# nglight-mini.net
KiCad netlist of a schematic drawn in EAGLE
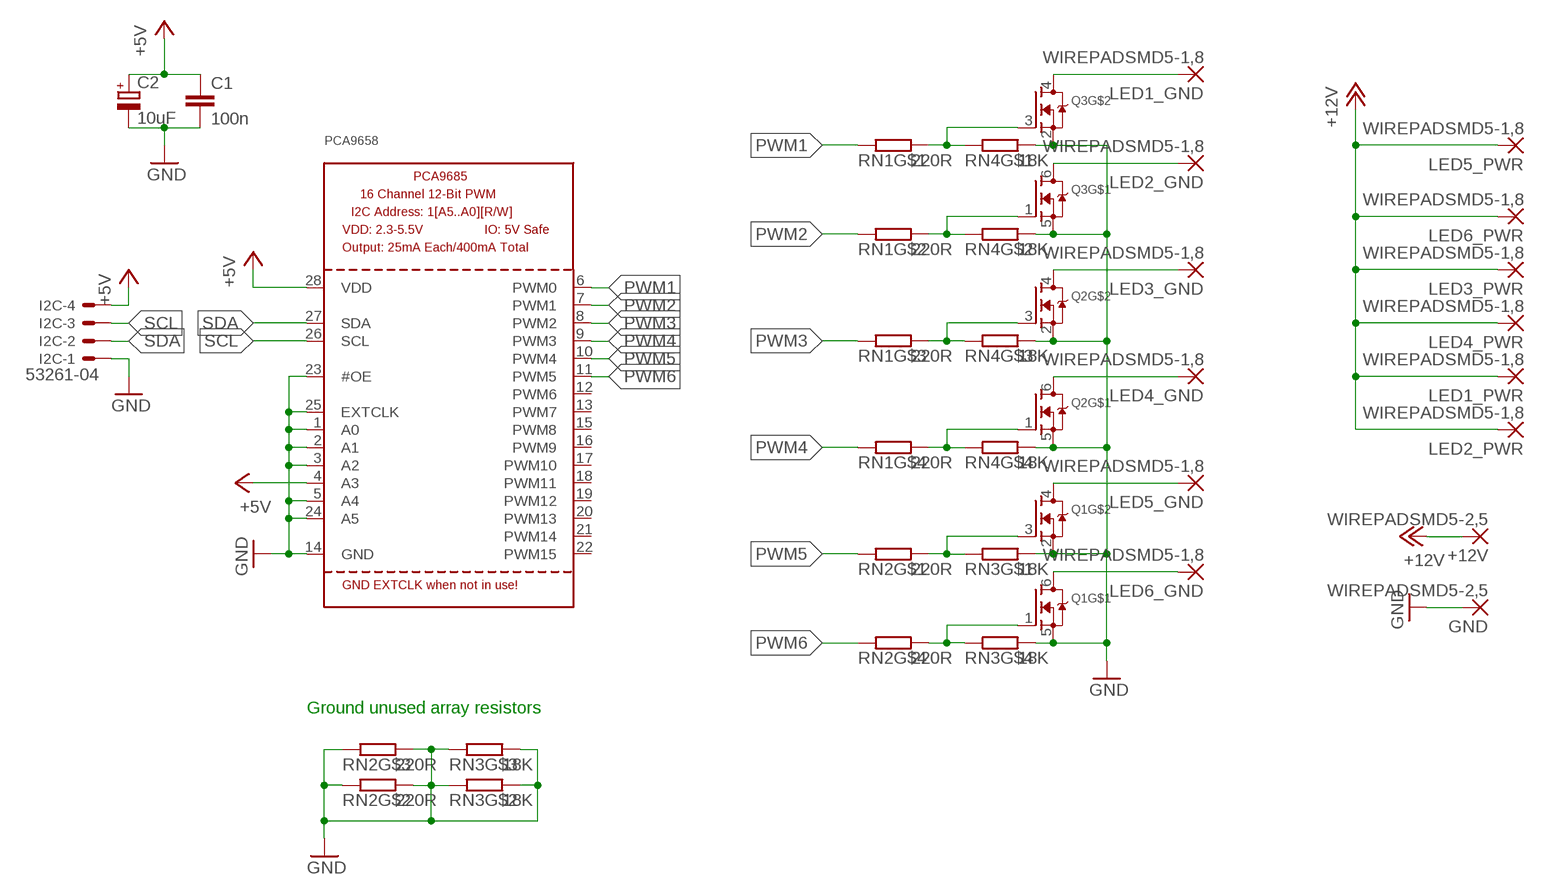
[diagram p0: schematic, sheet 1]

(export (version "E")
  (design (tool "Eeschema 10.0.6"))
  (components
    (comp (ref "+12V")
      (value "WIREPADSMD5-2,5")
      (footprint "eagle-import:5-2,5")
      (libsource (lib "eagle-import") (part "WIREPADSMD5-2,5"))
    )
    (comp (ref "C1")
      (value "100n")
      (footprint "eagle-import:C0805")
      (libsource (lib "eagle-import") (part "C-EUC0805"))
    )
    (comp (ref "C2")
      (value "10uF")
      (footprint "eagle-import:UD-5X5,8_NICHICON")
      (libsource (lib "eagle-import") (part "CPOL-EUUD-5X5,8"))
    )
    (comp (ref "GND")
      (value "WIREPADSMD5-2,5")
      (footprint "eagle-import:5-2,5")
      (libsource (lib "eagle-import") (part "WIREPADSMD5-2,5"))
    )
    (comp (ref "I2C")
      (value "53261-04")
      (footprint "eagle-import:53261-04")
      (libsource (lib "eagle-import") (part "53?-04261"))
    )
    (comp (ref "LED1_GND")
      (value "WIREPADSMD5-1,8")
      (footprint "eagle-import:5-1,8")
      (libsource (lib "eagle-import") (part "WIREPADSMD5-1,8"))
    )
    (comp (ref "LED1_PWR")
      (value "WIREPADSMD5-1,8")
      (footprint "eagle-import:5-1,8")
      (libsource (lib "eagle-import") (part "WIREPADSMD5-1,8"))
    )
    (comp (ref "LED2_GND")
      (value "WIREPADSMD5-1,8")
      (footprint "eagle-import:5-1,8")
      (libsource (lib "eagle-import") (part "WIREPADSMD5-1,8"))
    )
    (comp (ref "LED2_PWR")
      (value "WIREPADSMD5-1,8")
      (footprint "eagle-import:5-1,8")
      (libsource (lib "eagle-import") (part "WIREPADSMD5-1,8"))
    )
    (comp (ref "LED3_GND")
      (value "WIREPADSMD5-1,8")
      (footprint "eagle-import:5-1,8")
      (libsource (lib "eagle-import") (part "WIREPADSMD5-1,8"))
    )
    (comp (ref "LED3_PWR")
      (value "WIREPADSMD5-1,8")
      (footprint "eagle-import:5-1,8")
      (libsource (lib "eagle-import") (part "WIREPADSMD5-1,8"))
    )
    (comp (ref "LED4_GND")
      (value "WIREPADSMD5-1,8")
      (footprint "eagle-import:5-1,8")
      (libsource (lib "eagle-import") (part "WIREPADSMD5-1,8"))
    )
    (comp (ref "LED4_PWR")
      (value "WIREPADSMD5-1,8")
      (footprint "eagle-import:5-1,8")
      (libsource (lib "eagle-import") (part "WIREPADSMD5-1,8"))
    )
    (comp (ref "LED5_GND")
      (value "WIREPADSMD5-1,8")
      (footprint "eagle-import:5-1,8")
      (libsource (lib "eagle-import") (part "WIREPADSMD5-1,8"))
    )
    (comp (ref "LED5_PWR")
      (value "WIREPADSMD5-1,8")
      (footprint "eagle-import:5-1,8")
      (libsource (lib "eagle-import") (part "WIREPADSMD5-1,8"))
    )
    (comp (ref "LED6_GND")
      (value "WIREPADSMD5-1,8")
      (footprint "eagle-import:5-1,8")
      (libsource (lib "eagle-import") (part "WIREPADSMD5-1,8"))
    )
    (comp (ref "LED6_PWR")
      (value "WIREPADSMD5-1,8")
      (footprint "eagle-import:5-1,8")
      (libsource (lib "eagle-import") (part "WIREPADSMD5-1,8"))
    )
    (comp (ref "PCA9658")
      (value "PCA9685")
      (footprint "eagle-import:TSSOP28")
      (libsource (lib "eagle-import") (part "PCA9685"))
    )
    (comp (ref "Q1")
      (value "MOSFET-N")
      (footprint "eagle-import:SOT23-6")
      (libsource (lib "eagle-import") (part "MOSFET-N"))
    )
    (comp (ref "Q2")
      (value "MOSFET-N")
      (footprint "eagle-import:SOT23-6")
      (libsource (lib "eagle-import") (part "MOSFET-N"))
    )
    (comp (ref "Q3")
      (value "MOSFET-N")
      (footprint "eagle-import:SOT23-6")
      (libsource (lib "eagle-import") (part "MOSFET-N"))
    )
    (comp (ref "RN1")
      (value "220R")
      (footprint "eagle-import:0603_ARRAY_4")
      (libsource (lib "eagle-import") (part "4_RES_ARRAY"))
    )
    (comp (ref "RN2")
      (value "220R")
      (footprint "eagle-import:0603_ARRAY_4")
      (libsource (lib "eagle-import") (part "4_RES_ARRAY"))
    )
    (comp (ref "RN3")
      (value "18K")
      (footprint "eagle-import:0603_ARRAY_4")
      (libsource (lib "eagle-import") (part "4_RES_ARRAY"))
    )
    (comp (ref "RN4")
      (value "18K")
      (footprint "eagle-import:0603_ARRAY_4")
      (libsource (lib "eagle-import") (part "4_RES_ARRAY"))
    )
  )
  (nets
    (net (code "1") (name "+5V") (class "Default")
      (node (ref "C1") (pin "1") (pinfunction "1_1") (pintype "passive"))
      (node (ref "C2") (pin "+") (pinfunction "+_+") (pintype "passive"))
      (node (ref "I2C") (pin "4") (pinfunction "S_4") (pintype "passive"))
      (node (ref "PCA9658") (pin "28") (pinfunction "VDD_28") (pintype "power_in"))
      (node (ref "PCA9658") (pin "4") (pinfunction "A3_4") (pintype "bidirectional"))
    )
    (net (code "2") (name "+12V") (class "Default")
      (node (ref "+12V") (pin "1") (pinfunction "P_1") (pintype "passive"))
      (node (ref "LED1_PWR") (pin "1") (pinfunction "P_1") (pintype "passive"))
      (node (ref "LED2_PWR") (pin "1") (pinfunction "P_1") (pintype "passive"))
      (node (ref "LED3_PWR") (pin "1") (pinfunction "P_1") (pintype "passive"))
      (node (ref "LED4_PWR") (pin "1") (pinfunction "P_1") (pintype "passive"))
      (node (ref "LED5_PWR") (pin "1") (pinfunction "P_1") (pintype "passive"))
      (node (ref "LED6_PWR") (pin "1") (pinfunction "P_1") (pintype "passive"))
    )
    (net (code "3") (name "GND") (class "Default")
      (node (ref "C1") (pin "2") (pinfunction "2_2") (pintype "passive"))
      (node (ref "C2") (pin "-") (pinfunction "-_-") (pintype "passive"))
      (node (ref "GND") (pin "1") (pinfunction "P_1") (pintype "passive"))
      (node (ref "I2C") (pin "1") (pinfunction "S_1") (pintype "passive"))
      (node (ref "PCA9658") (pin "1") (pinfunction "A0_1") (pintype "bidirectional"))
      (node (ref "PCA9658") (pin "14") (pinfunction "GND_14") (pintype "power_in"))
      (node (ref "PCA9658") (pin "2") (pinfunction "A1_2") (pintype "bidirectional"))
      (node (ref "PCA9658") (pin "23") (pinfunction "#OE_23") (pintype "input"))
      (node (ref "PCA9658") (pin "24") (pinfunction "A5_24") (pintype "bidirectional"))
      (node (ref "PCA9658") (pin "25") (pinfunction "EXTCLK_25") (pintype "input"))
      (node (ref "PCA9658") (pin "3") (pinfunction "A2_3") (pintype "bidirectional"))
      (node (ref "PCA9658") (pin "5") (pinfunction "A4_5") (pintype "bidirectional"))
      (node (ref "Q1") (pin "2") (pinfunction "S_2") (pintype "bidirectional"))
      (node (ref "Q1") (pin "5") (pinfunction "S_5") (pintype "bidirectional"))
      (node (ref "Q2") (pin "2") (pinfunction "S_2") (pintype "bidirectional"))
      (node (ref "Q2") (pin "5") (pinfunction "S_5") (pintype "bidirectional"))
      (node (ref "Q3") (pin "2") (pinfunction "S_2") (pintype "bidirectional"))
      (node (ref "Q3") (pin "5") (pinfunction "S_5") (pintype "bidirectional"))
      (node (ref "RN2") (pin "2") (pinfunction "P$1_2") (pintype "passive"))
      (node (ref "RN2") (pin "3") (pinfunction "P$1_3") (pintype "passive"))
      (node (ref "RN2") (pin "6") (pinfunction "P$2_6") (pintype "passive"))
      (node (ref "RN2") (pin "7") (pinfunction "P$2_7") (pintype "passive"))
      (node (ref "RN3") (pin "2") (pinfunction "P$1_2") (pintype "passive"))
      (node (ref "RN3") (pin "3") (pinfunction "P$1_3") (pintype "passive"))
      (node (ref "RN3") (pin "5") (pinfunction "P$2_5") (pintype "passive"))
      (node (ref "RN3") (pin "6") (pinfunction "P$2_6") (pintype "passive"))
      (node (ref "RN3") (pin "7") (pinfunction "P$2_7") (pintype "passive"))
      (node (ref "RN3") (pin "8") (pinfunction "P$2_8") (pintype "passive"))
      (node (ref "RN4") (pin "5") (pinfunction "P$2_5") (pintype "passive"))
      (node (ref "RN4") (pin "6") (pinfunction "P$2_6") (pintype "passive"))
      (node (ref "RN4") (pin "7") (pinfunction "P$2_7") (pintype "passive"))
      (node (ref "RN4") (pin "8") (pinfunction "P$2_8") (pintype "passive"))
    )
    (net (code "4") (name "Net-(LED1_GND-P)") (class "Default")
      (node (ref "LED1_GND") (pin "1") (pinfunction "P_1") (pintype "passive"))
      (node (ref "Q3") (pin "4") (pinfunction "D_4") (pintype "bidirectional"))
    )
    (net (code "5") (name "Net-(LED2_GND-P)") (class "Default")
      (node (ref "LED2_GND") (pin "1") (pinfunction "P_1") (pintype "passive"))
      (node (ref "Q3") (pin "6") (pinfunction "D_6") (pintype "bidirectional"))
    )
    (net (code "6") (name "Net-(LED3_GND-P)") (class "Default")
      (node (ref "LED3_GND") (pin "1") (pinfunction "P_1") (pintype "passive"))
      (node (ref "Q2") (pin "4") (pinfunction "D_4") (pintype "bidirectional"))
    )
    (net (code "7") (name "Net-(LED4_GND-P)") (class "Default")
      (node (ref "LED4_GND") (pin "1") (pinfunction "P_1") (pintype "passive"))
      (node (ref "Q2") (pin "6") (pinfunction "D_6") (pintype "bidirectional"))
    )
    (net (code "8") (name "Net-(LED5_GND-P)") (class "Default")
      (node (ref "LED5_GND") (pin "1") (pinfunction "P_1") (pintype "passive"))
      (node (ref "Q1") (pin "4") (pinfunction "D_4") (pintype "bidirectional"))
    )
    (net (code "9") (name "Net-(LED6_GND-P)") (class "Default")
      (node (ref "LED6_GND") (pin "1") (pinfunction "P_1") (pintype "passive"))
      (node (ref "Q1") (pin "6") (pinfunction "D_6") (pintype "bidirectional"))
    )
    (net (code "10") (name "Net-(Q1A-G)") (class "Default")
      (node (ref "Q1") (pin "1") (pinfunction "G_1") (pintype "bidirectional"))
      (node (ref "RN2") (pin "5") (pinfunction "P$2_5") (pintype "passive"))
      (node (ref "RN3") (pin "4") (pinfunction "P$1_4") (pintype "passive"))
    )
    (net (code "11") (name "Net-(Q1B-G)") (class "Default")
      (node (ref "Q1") (pin "3") (pinfunction "G_3") (pintype "bidirectional"))
      (node (ref "RN2") (pin "8") (pinfunction "P$2_8") (pintype "passive"))
      (node (ref "RN3") (pin "1") (pinfunction "P$1_1") (pintype "passive"))
    )
    (net (code "12") (name "Net-(Q2A-G)") (class "Default")
      (node (ref "Q2") (pin "1") (pinfunction "G_1") (pintype "bidirectional"))
      (node (ref "RN1") (pin "5") (pinfunction "P$2_5") (pintype "passive"))
      (node (ref "RN4") (pin "4") (pinfunction "P$1_4") (pintype "passive"))
    )
    (net (code "13") (name "Net-(Q2B-G)") (class "Default")
      (node (ref "Q2") (pin "3") (pinfunction "G_3") (pintype "bidirectional"))
      (node (ref "RN1") (pin "6") (pinfunction "P$2_6") (pintype "passive"))
      (node (ref "RN4") (pin "3") (pinfunction "P$1_3") (pintype "passive"))
    )
    (net (code "14") (name "Net-(Q3A-G)") (class "Default")
      (node (ref "Q3") (pin "1") (pinfunction "G_1") (pintype "bidirectional"))
      (node (ref "RN1") (pin "7") (pinfunction "P$2_7") (pintype "passive"))
      (node (ref "RN4") (pin "2") (pinfunction "P$1_2") (pintype "passive"))
    )
    (net (code "15") (name "Net-(Q3B-G)") (class "Default")
      (node (ref "Q3") (pin "3") (pinfunction "G_3") (pintype "bidirectional"))
      (node (ref "RN1") (pin "8") (pinfunction "P$2_8") (pintype "passive"))
      (node (ref "RN4") (pin "1") (pinfunction "P$1_1") (pintype "passive"))
    )
    (net (code "16") (name "PWM1") (class "Default")
      (node (ref "PCA9658") (pin "6") (pinfunction "PWM0_6") (pintype "output"))
      (node (ref "RN1") (pin "1") (pinfunction "P$1_1") (pintype "passive"))
    )
    (net (code "17") (name "PWM2") (class "Default")
      (node (ref "PCA9658") (pin "7") (pinfunction "PWM1_7") (pintype "output"))
      (node (ref "RN1") (pin "2") (pinfunction "P$1_2") (pintype "passive"))
    )
    (net (code "18") (name "PWM3") (class "Default")
      (node (ref "PCA9658") (pin "8") (pinfunction "PWM2_8") (pintype "output"))
      (node (ref "RN1") (pin "3") (pinfunction "P$1_3") (pintype "passive"))
    )
    (net (code "19") (name "PWM4") (class "Default")
      (node (ref "PCA9658") (pin "9") (pinfunction "PWM3_9") (pintype "output"))
      (node (ref "RN1") (pin "4") (pinfunction "P$1_4") (pintype "passive"))
    )
    (net (code "20") (name "PWM5") (class "Default")
      (node (ref "PCA9658") (pin "10") (pinfunction "PWM4_10") (pintype "output"))
      (node (ref "RN2") (pin "1") (pinfunction "P$1_1") (pintype "passive"))
    )
    (net (code "21") (name "PWM6") (class "Default")
      (node (ref "PCA9658") (pin "11") (pinfunction "PWM5_11") (pintype "output"))
      (node (ref "RN2") (pin "4") (pinfunction "P$1_4") (pintype "passive"))
    )
    (net (code "22") (name "SCL") (class "Default")
      (node (ref "I2C") (pin "3") (pinfunction "S_3") (pintype "passive"))
      (node (ref "PCA9658") (pin "26") (pinfunction "SCL_26") (pintype "bidirectional"))
    )
    (net (code "23") (name "SDA") (class "Default")
      (node (ref "I2C") (pin "2") (pinfunction "S_2") (pintype "passive"))
      (node (ref "PCA9658") (pin "27") (pinfunction "SDA_27") (pintype "bidirectional"))
    )
    (net (code "24") (name "unconnected-(PCA9658-PWM6-Pad12)") (class "Default")
      (node (ref "PCA9658") (pin "12") (pinfunction "PWM6_12") (pintype "output"))
    )
    (net (code "25") (name "unconnected-(PCA9658-PWM7-Pad13)") (class "Default")
      (node (ref "PCA9658") (pin "13") (pinfunction "PWM7_13") (pintype "output"))
    )
    (net (code "26") (name "unconnected-(PCA9658-PWM8-Pad15)") (class "Default")
      (node (ref "PCA9658") (pin "15") (pinfunction "PWM8_15") (pintype "output"))
    )
    (net (code "27") (name "unconnected-(PCA9658-PWM9-Pad16)") (class "Default")
      (node (ref "PCA9658") (pin "16") (pinfunction "PWM9_16") (pintype "output"))
    )
    (net (code "28") (name "unconnected-(PCA9658-PWM10-Pad17)") (class "Default")
      (node (ref "PCA9658") (pin "17") (pinfunction "PWM10_17") (pintype "output"))
    )
    (net (code "29") (name "unconnected-(PCA9658-PWM11-Pad18)") (class "Default")
      (node (ref "PCA9658") (pin "18") (pinfunction "PWM11_18") (pintype "output"))
    )
    (net (code "30") (name "unconnected-(PCA9658-PWM12-Pad19)") (class "Default")
      (node (ref "PCA9658") (pin "19") (pinfunction "PWM12_19") (pintype "output"))
    )
    (net (code "31") (name "unconnected-(PCA9658-PWM13-Pad20)") (class "Default")
      (node (ref "PCA9658") (pin "20") (pinfunction "PWM13_20") (pintype "output"))
    )
    (net (code "32") (name "unconnected-(PCA9658-PWM14-Pad21)") (class "Default")
      (node (ref "PCA9658") (pin "21") (pinfunction "PWM14_21") (pintype "output"))
    )
    (net (code "33") (name "unconnected-(PCA9658-PWM15-Pad22)") (class "Default")
      (node (ref "PCA9658") (pin "22") (pinfunction "PWM15_22") (pintype "output"))
    )
  )
)
